# A32_to_Samtec50mil.net
KiCad netlist of a schematic drawn in EAGLE
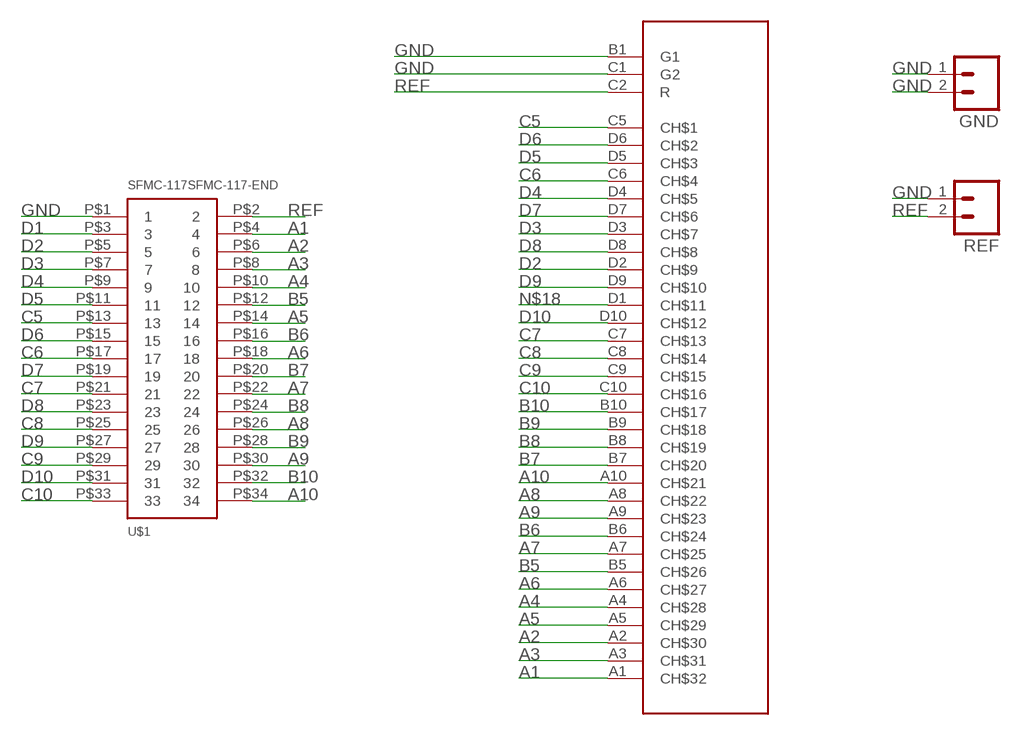
[diagram p0: schematic, sheet 1]

(export (version "E")
  (design (tool "Eeschema 10.0.6"))
  (components
    (comp (ref "GND")
      (value "M02PTH")
      (footprint "eagle-import:1X02")
      (libsource (lib "eagle-import") (part "M02PTH"))
    )
    (comp (ref "REF")
      (value "M02PTH")
      (footprint "eagle-import:1X02")
      (libsource (lib "eagle-import") (part "M02PTH"))
    )
    (comp (ref "U$1")
      (value "SFMC-117SFMC-117-END")
      (footprint "eagle-import:SFMC-117-END")
      (libsource (lib "eagle-import") (part "SFMC-117SFMC-117-END"))
    )
    (comp (ref "U$2")
      (value "NEURONEXUS-A32")
      (footprint "eagle-import:ROLC-110-XX-XX-Q-LC")
      (libsource (lib "eagle-import") (part "NEURONEXUS-A32"))
    )
  )
  (nets
    (net (code "1") (name "/A1") (class "Default")
      (node (ref "U$1") (pin "P$4") (pinfunction "4_P$4") (pintype "bidirectional"))
      (node (ref "U$2") (pin "A1") (pinfunction "CH$32_A1") (pintype "bidirectional"))
    )
    (net (code "2") (name "/A2") (class "Default")
      (node (ref "U$1") (pin "P$6") (pinfunction "6_P$6") (pintype "bidirectional"))
      (node (ref "U$2") (pin "A2") (pinfunction "CH$30_A2") (pintype "bidirectional"))
    )
    (net (code "3") (name "/A3") (class "Default")
      (node (ref "U$1") (pin "P$8") (pinfunction "8_P$8") (pintype "bidirectional"))
      (node (ref "U$2") (pin "A3") (pinfunction "CH$31_A3") (pintype "bidirectional"))
    )
    (net (code "4") (name "/A4") (class "Default")
      (node (ref "U$1") (pin "P$10") (pinfunction "10_P$10") (pintype "bidirectional"))
      (node (ref "U$2") (pin "A4") (pinfunction "CH$28_A4") (pintype "bidirectional"))
    )
    (net (code "5") (name "/A5") (class "Default")
      (node (ref "U$1") (pin "P$14") (pinfunction "14_P$14") (pintype "bidirectional"))
      (node (ref "U$2") (pin "A5") (pinfunction "CH$29_A5") (pintype "bidirectional"))
    )
    (net (code "6") (name "/A6") (class "Default")
      (node (ref "U$1") (pin "P$18") (pinfunction "18_P$18") (pintype "bidirectional"))
      (node (ref "U$2") (pin "A6") (pinfunction "CH$27_A6") (pintype "bidirectional"))
    )
    (net (code "7") (name "/A7") (class "Default")
      (node (ref "U$1") (pin "P$22") (pinfunction "22_P$22") (pintype "bidirectional"))
      (node (ref "U$2") (pin "A7") (pinfunction "CH$25_A7") (pintype "bidirectional"))
    )
    (net (code "8") (name "/A8") (class "Default")
      (node (ref "U$1") (pin "P$26") (pinfunction "26_P$26") (pintype "bidirectional"))
      (node (ref "U$2") (pin "A8") (pinfunction "CH$22_A8") (pintype "bidirectional"))
    )
    (net (code "9") (name "/A9") (class "Default")
      (node (ref "U$1") (pin "P$30") (pinfunction "30_P$30") (pintype "bidirectional"))
      (node (ref "U$2") (pin "A9") (pinfunction "CH$23_A9") (pintype "bidirectional"))
    )
    (net (code "10") (name "/A10") (class "Default")
      (node (ref "U$1") (pin "P$34") (pinfunction "34_P$34") (pintype "bidirectional"))
      (node (ref "U$2") (pin "A10") (pinfunction "CH$21_A10") (pintype "bidirectional"))
    )
    (net (code "11") (name "/B5") (class "Default")
      (node (ref "U$1") (pin "P$12") (pinfunction "12_P$12") (pintype "bidirectional"))
      (node (ref "U$2") (pin "B5") (pinfunction "CH$26_B5") (pintype "bidirectional"))
    )
    (net (code "12") (name "/B6") (class "Default")
      (node (ref "U$1") (pin "P$16") (pinfunction "16_P$16") (pintype "bidirectional"))
      (node (ref "U$2") (pin "B6") (pinfunction "CH$24_B6") (pintype "bidirectional"))
    )
    (net (code "13") (name "/B7") (class "Default")
      (node (ref "U$1") (pin "P$20") (pinfunction "20_P$20") (pintype "bidirectional"))
      (node (ref "U$2") (pin "B7") (pinfunction "CH$20_B7") (pintype "bidirectional"))
    )
    (net (code "14") (name "/B8") (class "Default")
      (node (ref "U$1") (pin "P$24") (pinfunction "24_P$24") (pintype "bidirectional"))
      (node (ref "U$2") (pin "B8") (pinfunction "CH$19_B8") (pintype "bidirectional"))
    )
    (net (code "15") (name "/B9") (class "Default")
      (node (ref "U$1") (pin "P$28") (pinfunction "28_P$28") (pintype "bidirectional"))
      (node (ref "U$2") (pin "B9") (pinfunction "CH$18_B9") (pintype "bidirectional"))
    )
    (net (code "16") (name "/B10") (class "Default")
      (node (ref "U$1") (pin "P$32") (pinfunction "32_P$32") (pintype "bidirectional"))
      (node (ref "U$2") (pin "B10") (pinfunction "CH$17_B10") (pintype "bidirectional"))
    )
    (net (code "17") (name "/C5") (class "Default")
      (node (ref "U$1") (pin "P$13") (pinfunction "13_P$13") (pintype "bidirectional"))
      (node (ref "U$2") (pin "C5") (pinfunction "CH$1_C5") (pintype "bidirectional"))
    )
    (net (code "18") (name "/C6") (class "Default")
      (node (ref "U$1") (pin "P$17") (pinfunction "17_P$17") (pintype "bidirectional"))
      (node (ref "U$2") (pin "C6") (pinfunction "CH$4_C6") (pintype "bidirectional"))
    )
    (net (code "19") (name "/C7") (class "Default")
      (node (ref "U$1") (pin "P$21") (pinfunction "21_P$21") (pintype "bidirectional"))
      (node (ref "U$2") (pin "C7") (pinfunction "CH$13_C7") (pintype "bidirectional"))
    )
    (net (code "20") (name "/C8") (class "Default")
      (node (ref "U$1") (pin "P$25") (pinfunction "25_P$25") (pintype "bidirectional"))
      (node (ref "U$2") (pin "C8") (pinfunction "CH$14_C8") (pintype "bidirectional"))
    )
    (net (code "21") (name "/C9") (class "Default")
      (node (ref "U$1") (pin "P$29") (pinfunction "29_P$29") (pintype "bidirectional"))
      (node (ref "U$2") (pin "C9") (pinfunction "CH$15_C9") (pintype "bidirectional"))
    )
    (net (code "22") (name "/C10") (class "Default")
      (node (ref "U$1") (pin "P$33") (pinfunction "33_P$33") (pintype "bidirectional"))
      (node (ref "U$2") (pin "C10") (pinfunction "CH$16_C10") (pintype "bidirectional"))
    )
    (net (code "23") (name "/D1") (class "Default")
      (node (ref "U$1") (pin "P$3") (pinfunction "3_P$3") (pintype "bidirectional"))
    )
    (net (code "24") (name "/D2") (class "Default")
      (node (ref "U$1") (pin "P$5") (pinfunction "5_P$5") (pintype "bidirectional"))
      (node (ref "U$2") (pin "D2") (pinfunction "CH$9_D2") (pintype "bidirectional"))
    )
    (net (code "25") (name "/D3") (class "Default")
      (node (ref "U$1") (pin "P$7") (pinfunction "7_P$7") (pintype "bidirectional"))
      (node (ref "U$2") (pin "D3") (pinfunction "CH$7_D3") (pintype "bidirectional"))
    )
    (net (code "26") (name "/D4") (class "Default")
      (node (ref "U$1") (pin "P$9") (pinfunction "9_P$9") (pintype "bidirectional"))
      (node (ref "U$2") (pin "D4") (pinfunction "CH$5_D4") (pintype "bidirectional"))
    )
    (net (code "27") (name "/D5") (class "Default")
      (node (ref "U$1") (pin "P$11") (pinfunction "11_P$11") (pintype "bidirectional"))
      (node (ref "U$2") (pin "D5") (pinfunction "CH$3_D5") (pintype "bidirectional"))
    )
    (net (code "28") (name "/D6") (class "Default")
      (node (ref "U$1") (pin "P$15") (pinfunction "15_P$15") (pintype "bidirectional"))
      (node (ref "U$2") (pin "D6") (pinfunction "CH$2_D6") (pintype "bidirectional"))
    )
    (net (code "29") (name "/D7") (class "Default")
      (node (ref "U$1") (pin "P$19") (pinfunction "19_P$19") (pintype "bidirectional"))
      (node (ref "U$2") (pin "D7") (pinfunction "CH$6_D7") (pintype "bidirectional"))
    )
    (net (code "30") (name "/D8") (class "Default")
      (node (ref "U$1") (pin "P$23") (pinfunction "23_P$23") (pintype "bidirectional"))
      (node (ref "U$2") (pin "D8") (pinfunction "CH$8_D8") (pintype "bidirectional"))
    )
    (net (code "31") (name "/D9") (class "Default")
      (node (ref "U$1") (pin "P$27") (pinfunction "27_P$27") (pintype "bidirectional"))
      (node (ref "U$2") (pin "D9") (pinfunction "CH$10_D9") (pintype "bidirectional"))
    )
    (net (code "32") (name "/D10") (class "Default")
      (node (ref "U$1") (pin "P$31") (pinfunction "31_P$31") (pintype "bidirectional"))
      (node (ref "U$2") (pin "D10") (pinfunction "CH$12_D10") (pintype "bidirectional"))
    )
    (net (code "33") (name "/GND") (class "Default")
      (node (ref "GND") (pin "1") (pinfunction "1_1") (pintype "passive"))
      (node (ref "GND") (pin "2") (pinfunction "2_2") (pintype "passive"))
      (node (ref "REF") (pin "1") (pinfunction "1_1") (pintype "passive"))
      (node (ref "U$1") (pin "P$1") (pinfunction "1_P$1") (pintype "bidirectional"))
      (node (ref "U$2") (pin "B1") (pinfunction "G1_B1") (pintype "bidirectional"))
      (node (ref "U$2") (pin "C1") (pinfunction "G2_C1") (pintype "bidirectional"))
    )
    (net (code "34") (name "/N$18") (class "Default")
      (node (ref "U$2") (pin "D1") (pinfunction "CH$11_D1") (pintype "bidirectional"))
    )
    (net (code "35") (name "/REF") (class "Default")
      (node (ref "REF") (pin "2") (pinfunction "2_2") (pintype "passive"))
      (node (ref "U$1") (pin "P$2") (pinfunction "2_P$2") (pintype "bidirectional"))
      (node (ref "U$2") (pin "C2") (pinfunction "R_C2") (pintype "bidirectional"))
    )
  )
)
